# main.net
KiCad netlist of a schematic drawn in Altium Designer
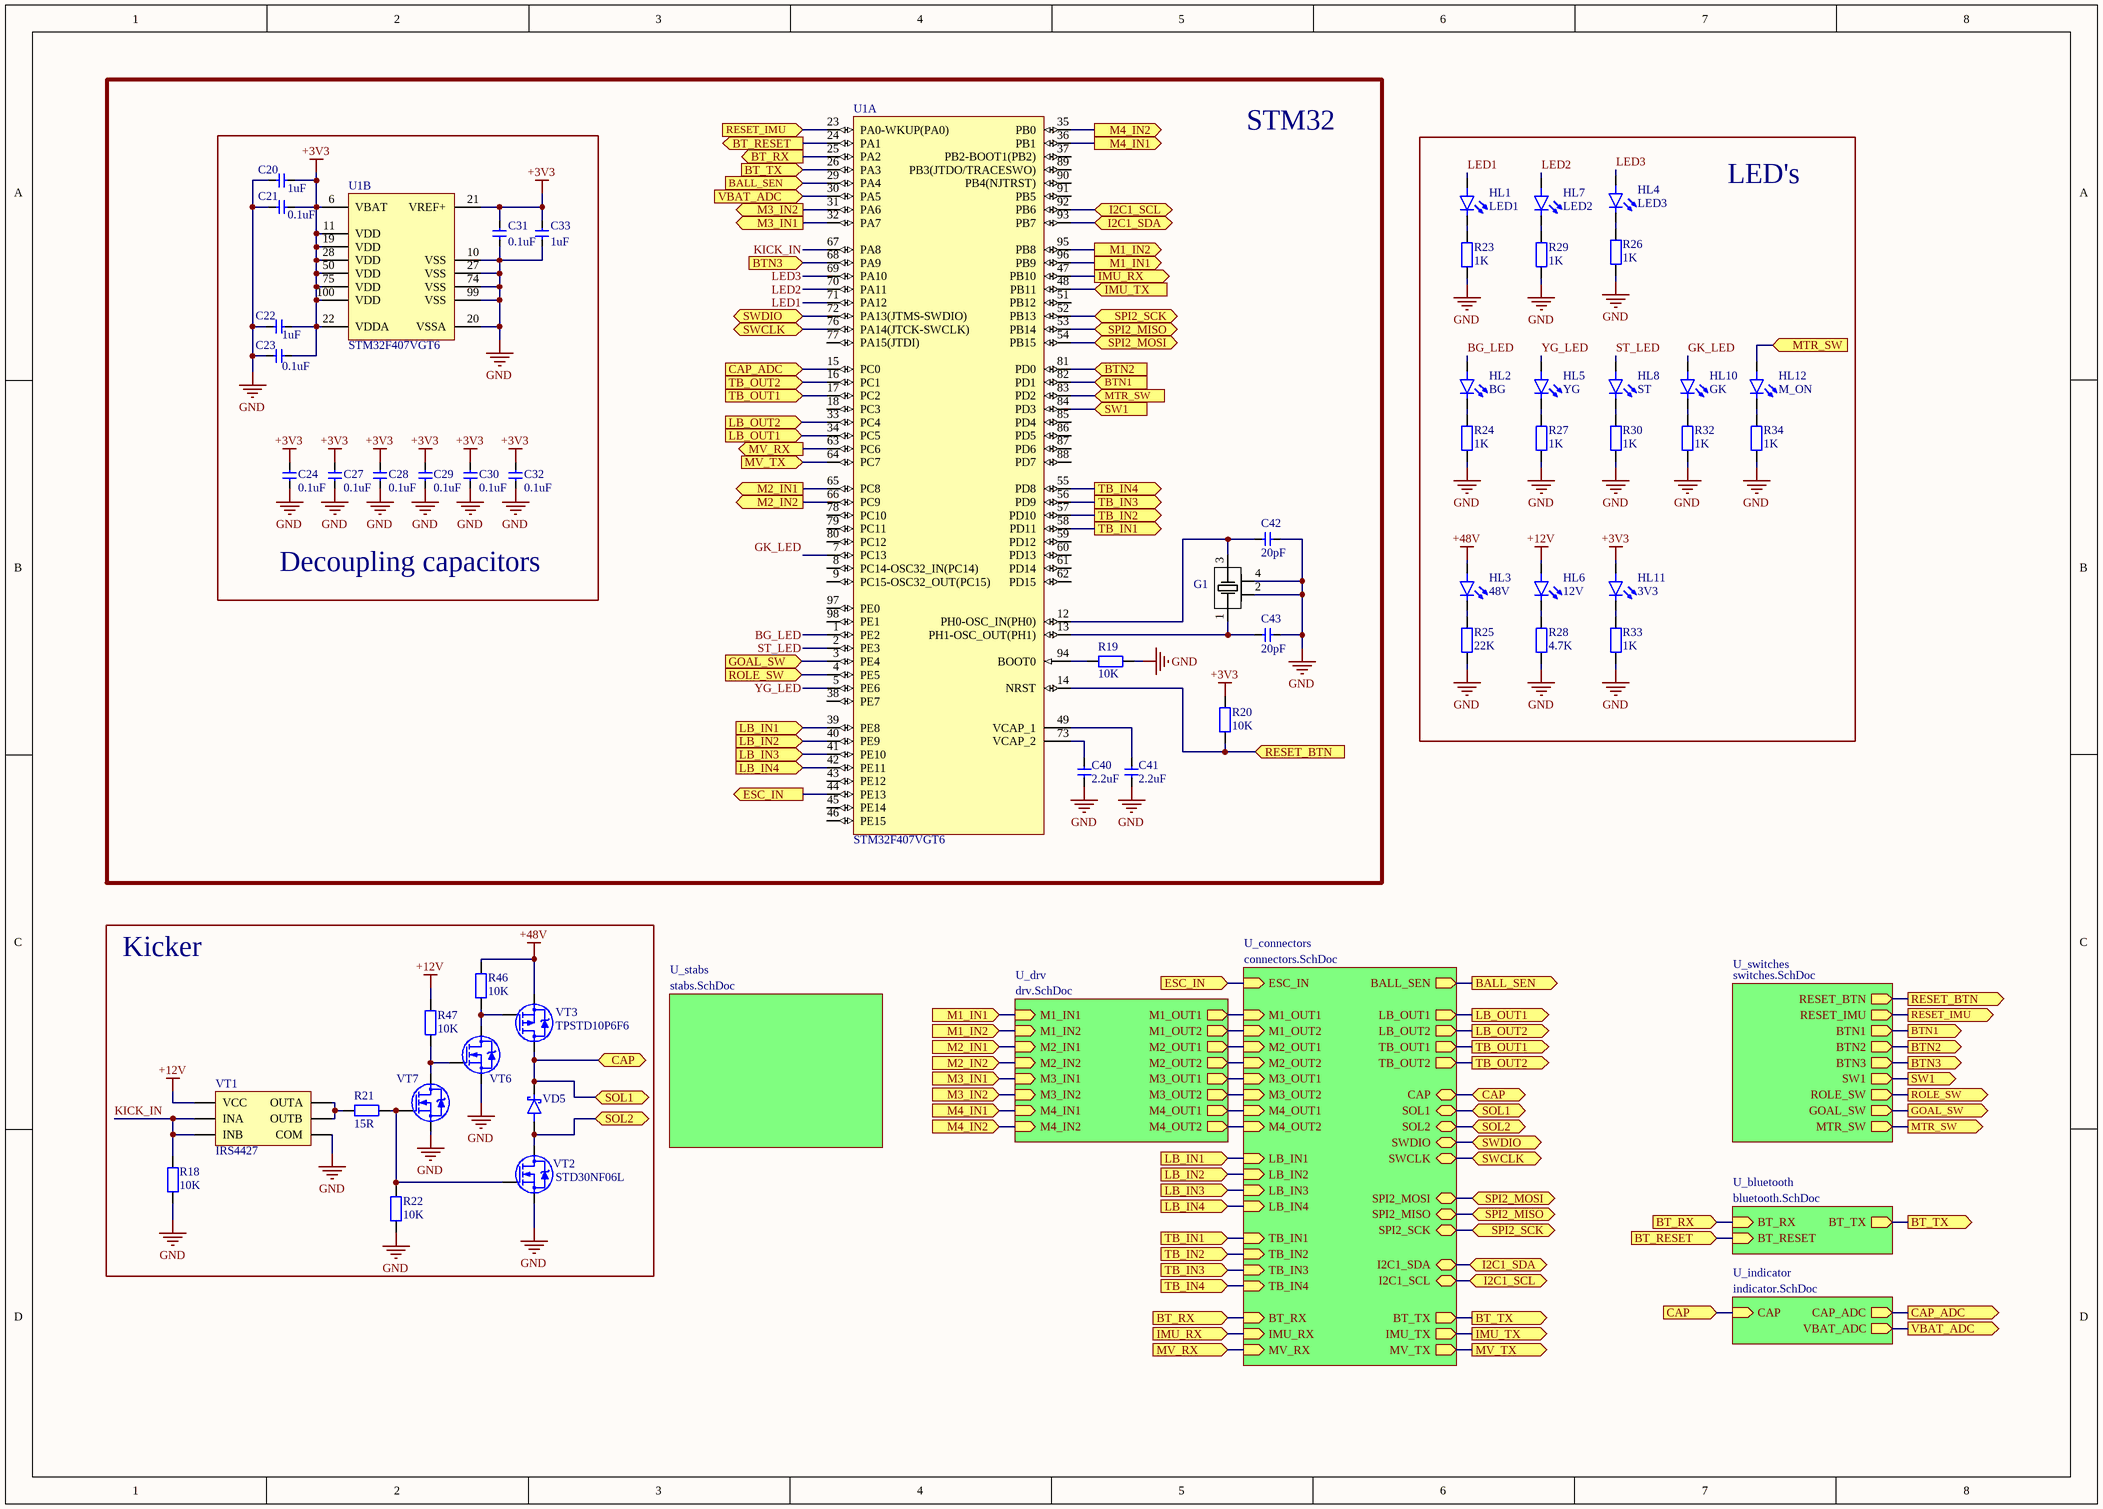
[diagram p0: main.SchDoc]

(export (version "E")
  (design (tool "Eeschema 10.0.6"))
  (components
    (comp (ref "C20")
      (value "1uF")
      (footprint "CAP0805")
      (description "Ceramic SMD Cap")
      (libsource (lib "") (part "CAP Ceramic_1"))
    )
    (comp (ref "C21")
      (value "0.1uF")
      (footprint "CAP0805")
      (description "Ceramic SMD Cap")
      (libsource (lib "") (part "CAP Ceramic_1"))
    )
    (comp (ref "C22")
      (value "1uF")
      (footprint "CAP0805")
      (description "Ceramic SMD Cap")
      (libsource (lib "") (part "CAP Ceramic_1"))
    )
    (comp (ref "C23")
      (value "0.1uF")
      (footprint "CAP0805")
      (description "Ceramic SMD Cap")
      (libsource (lib "") (part "CAP Ceramic_1"))
    )
    (comp (ref "C24")
      (value "0.1uF")
      (footprint "CAP0805")
      (description "Ceramic SMD Cap")
      (libsource (lib "") (part "CAP Ceramic_1"))
    )
    (comp (ref "C27")
      (value "0.1uF")
      (footprint "CAP0805")
      (description "Ceramic SMD Cap")
      (libsource (lib "") (part "CAP Ceramic_1"))
    )
    (comp (ref "C28")
      (value "0.1uF")
      (footprint "CAP0805")
      (description "Ceramic SMD Cap")
      (libsource (lib "") (part "CAP Ceramic_1"))
    )
    (comp (ref "C29")
      (value "0.1uF")
      (footprint "CAP0805")
      (description "Ceramic SMD Cap")
      (libsource (lib "") (part "CAP Ceramic_1"))
    )
    (comp (ref "C30")
      (value "0.1uF")
      (footprint "CAP0805")
      (description "Ceramic SMD Cap")
      (libsource (lib "") (part "CAP Ceramic_1"))
    )
    (comp (ref "C31")
      (value "0.1uF")
      (footprint "CAP0805")
      (description "Ceramic SMD Cap")
      (libsource (lib "") (part "CAP Ceramic_1"))
    )
    (comp (ref "C32")
      (value "0.1uF")
      (footprint "CAP0805")
      (description "Ceramic SMD Cap")
      (libsource (lib "") (part "CAP Ceramic_1"))
    )
    (comp (ref "C33")
      (value "1uF")
      (footprint "CAP0805")
      (description "Ceramic SMD Cap")
      (libsource (lib "") (part "CAP Ceramic_1"))
    )
    (comp (ref "C40")
      (value "2.2uF")
      (footprint "CAP0805")
      (description "Ceramic SMD Cap")
      (libsource (lib "Asterisk") (part "CAP Ceramic"))
    )
    (comp (ref "C41")
      (value "2.2uF")
      (footprint "CAP0805")
      (description "Ceramic SMD Cap")
      (libsource (lib "Asterisk") (part "CAP Ceramic"))
    )
    (comp (ref "C42")
      (value "20pF")
      (footprint "CAP0805")
      (description "Ceramic SMD Cap")
      (libsource (lib "") (part "CAP Ceramic_1"))
    )
    (comp (ref "C43")
      (value "20pF")
      (footprint "CAP0805")
      (description "Ceramic SMD Cap")
      (libsource (lib "") (part "CAP Ceramic_1"))
    )
    (comp (ref "G1")
      (value "8 MHz")
      (footprint "TSX-3225")
      (description "24MHz ±10ppm Crystal 9pF 40 Ohms 4-SMD, No Lead")
      (fields
        (field (name "PART NUMBER") "TSX-3225 24.0000MF15X-AC6")
        (field (name "DIGI-KEY PART NUMBER") "SER4180CT-ND")
      )
      (libsource (lib "SssAccesDatbase") (part "CTX957CT"))
    )
    (comp (ref "HL1")
      (value "LED1")
      (footprint "LED0603_WHITE")
      (description "LED smd")
      (libsource (lib "Asterisk") (part "LED"))
    )
    (comp (ref "HL2")
      (value "BG")
      (footprint "LED0603_WHITE")
      (description "LED smd")
      (libsource (lib "Asterisk") (part "LED"))
    )
    (comp (ref "HL3")
      (value "48V")
      (footprint "LED0603_GREEN")
      (description "LED smd")
      (libsource (lib "Asterisk") (part "LED"))
    )
    (comp (ref "HL4")
      (value "LED3")
      (footprint "LED0603_WHITE")
      (description "LED smd")
      (libsource (lib "Asterisk") (part "LED"))
    )
    (comp (ref "HL5")
      (value "YG")
      (footprint "LED0603_WHITE")
      (description "LED smd")
      (libsource (lib "Asterisk") (part "LED"))
    )
    (comp (ref "HL6")
      (value "12V")
      (footprint "LED0603_GREEN")
      (description "LED smd")
      (libsource (lib "Asterisk") (part "LED"))
    )
    (comp (ref "HL7")
      (value "LED2")
      (footprint "LED0603_WHITE")
      (description "LED smd")
      (libsource (lib "Asterisk") (part "LED"))
    )
    (comp (ref "HL8")
      (value "ST")
      (footprint "LED0603_WHITE")
      (description "LED smd")
      (libsource (lib "Asterisk") (part "LED"))
    )
    (comp (ref "HL10")
      (value "GK")
      (footprint "LED0603_WHITE")
      (description "LED smd")
      (libsource (lib "Asterisk") (part "LED"))
    )
    (comp (ref "HL11")
      (value "3V3")
      (footprint "LED0603_GREEN")
      (description "LED smd")
      (libsource (lib "Asterisk") (part "LED"))
    )
    (comp (ref "HL12")
      (value "M_ON")
      (footprint "LED0603_RED")
      (description "LED smd")
      (libsource (lib "Asterisk") (part "LED"))
    )
    (comp (ref "R18")
      (value "10K")
      (footprint "RES0805")
      (description "RES smd")
      (libsource (lib "Asterisk") (part "RES"))
    )
    (comp (ref "R19")
      (value "10K")
      (footprint "RES0805")
      (description "RES smd")
      (libsource (lib "Asterisk") (part "RES"))
    )
    (comp (ref "R20")
      (value "10K")
      (footprint "RES0805")
      (description "RES smd")
      (libsource (lib "Asterisk") (part "RES"))
    )
    (comp (ref "R21")
      (value "15R")
      (footprint "RES1206")
      (description "RES smd")
      (libsource (lib "Asterisk") (part "RES"))
    )
    (comp (ref "R22")
      (value "10K")
      (footprint "RES0805")
      (description "RES smd")
      (libsource (lib "Asterisk") (part "RES"))
    )
    (comp (ref "R23")
      (value "1K")
      (footprint "RES0805")
      (description "RES smd")
      (libsource (lib "Asterisk") (part "RES"))
    )
    (comp (ref "R24")
      (value "1K")
      (footprint "RES0805")
      (description "RES smd")
      (libsource (lib "Asterisk") (part "RES"))
    )
    (comp (ref "R25")
      (value "22K")
      (footprint "RES0805")
      (description "RES smd")
      (libsource (lib "Asterisk") (part "RES"))
    )
    (comp (ref "R26")
      (value "1K")
      (footprint "RES0805")
      (description "RES smd")
      (libsource (lib "Asterisk") (part "RES"))
    )
    (comp (ref "R27")
      (value "1K")
      (footprint "RES0805")
      (description "RES smd")
      (libsource (lib "Asterisk") (part "RES"))
    )
    (comp (ref "R28")
      (value "4.7K")
      (footprint "RES0805")
      (description "RES smd")
      (libsource (lib "Asterisk") (part "RES"))
    )
    (comp (ref "R29")
      (value "1K")
      (footprint "RES0805")
      (description "RES smd")
      (libsource (lib "Asterisk") (part "RES"))
    )
    (comp (ref "R30")
      (value "1K")
      (footprint "RES0805")
      (description "RES smd")
      (libsource (lib "Asterisk") (part "RES"))
    )
    (comp (ref "R32")
      (value "1K")
      (footprint "RES0805")
      (description "RES smd")
      (libsource (lib "Asterisk") (part "RES"))
    )
    (comp (ref "R33")
      (value "1K")
      (footprint "RES0805")
      (description "RES smd")
      (libsource (lib "Asterisk") (part "RES"))
    )
    (comp (ref "R34")
      (value "1K")
      (footprint "RES0805")
      (description "RES smd")
      (libsource (lib "Asterisk") (part "RES"))
    )
    (comp (ref "R46")
      (value "10K")
      (footprint "RES0805")
      (description "RES smd")
      (libsource (lib "Asterisk") (part "RES"))
    )
    (comp (ref "R47")
      (value "10K")
      (footprint "RES0805")
      (description "RES smd")
      (libsource (lib "Asterisk") (part "RES"))
    )
    (comp (ref "U1")
      (value "STM32F407VGT6")
      (footprint "LQFP100")
      (fields (field (name "MANUFACTURER") "STMicroelectronics"))
      (libsource (lib "Asterisk") (part "STM32F407VGT6"))
    )
    (comp (ref "VD5")
      (value "Diode Schottky")
      (footprint "DO-214AC (SMA)")
      (libsource (lib "Asterisk") (part "Diode Schottky"))
    )
    (comp (ref "VT1")
      (value "IRS4427")
      (footprint "SOIC-8")
      (description "Mosfet driver")
      (libsource (lib "Asterisk") (part "IRS4427"))
    )
    (comp (ref "VT2")
      (value "STD30NF06L")
      (footprint "DPAK")
      (description "N-MOSFET\r\nUds = 60 V\r\nIds = 30 A\r\nRds = 0.023 Ohm\r\nP = 55 W")
      (libsource (lib "Asterisk") (part "STD30NF06L"))
    )
    (comp (ref "VT3")
      (value "TPSTD10P6F6")
      (footprint "DPAK")
      (description "P-MOSFET\r\nUds = 60 V\r\nIds = 13 A\r\nRds = 0.100 Ohm\r\nP = 60 W")
      (libsource (lib "Asterisk") (part "TPSTD10P6F6"))
    )
    (comp (ref "VT6")
      (value "IRLML2502")
      (footprint "SOT-23-3")
      (description "N-MOSFET\r\nUds = 20 V\r\nIds = 4.2 A\r\nRds = 0.035 Ohm\r\nP = 1,25 W")
      (libsource (lib "Asterisk") (part "IRLML2502"))
    )
    (comp (ref "VT7")
      (value "IRLML2502")
      (footprint "SOT-23-3")
      (description "N-MOSFET\r\nUds = 20 V\r\nIds = 4.2 A\r\nRds = 0.035 Ohm\r\nP = 8 W")
      (libsource (lib "Asterisk") (part "IRLML2502"))
    )
  )
  (nets
    (net (code "1") (name "+3V3") (class "Default")
      (node (ref "C20") (pin "1") (pinfunction "1_1") (pintype "passive"))
      (node (ref "C21") (pin "1") (pinfunction "1_1") (pintype "passive"))
      (node (ref "C22") (pin "1") (pinfunction "1_1") (pintype "passive"))
      (node (ref "C23") (pin "1") (pinfunction "1_1") (pintype "passive"))
      (node (ref "C24") (pin "1") (pinfunction "1_1") (pintype "passive"))
      (node (ref "C27") (pin "1") (pinfunction "1_1") (pintype "passive"))
      (node (ref "C28") (pin "1") (pinfunction "1_1") (pintype "passive"))
      (node (ref "C29") (pin "1") (pinfunction "1_1") (pintype "passive"))
      (node (ref "C30") (pin "1") (pinfunction "1_1") (pintype "passive"))
      (node (ref "C31") (pin "2") (pinfunction "2_2") (pintype "passive"))
      (node (ref "C32") (pin "1") (pinfunction "1_1") (pintype "passive"))
      (node (ref "C33") (pin "2") (pinfunction "2_2") (pintype "passive"))
      (node (ref "HL11") (pin "2") (pinfunction "A_2") (pintype "passive"))
      (node (ref "R20") (pin "1") (pinfunction "1_1") (pintype "passive"))
      (node (ref "U1") (pin "100") (pinfunction "VDD_100") (pintype "power_in"))
      (node (ref "U1") (pin "11") (pinfunction "VDD_11") (pintype "power_in"))
      (node (ref "U1") (pin "19") (pinfunction "VDD_19") (pintype "power_in"))
      (node (ref "U1") (pin "21") (pinfunction "VREF+_21") (pintype "power_in"))
      (node (ref "U1") (pin "22") (pinfunction "VDDA_22") (pintype "power_in"))
      (node (ref "U1") (pin "28") (pinfunction "VDD_28") (pintype "power_in"))
      (node (ref "U1") (pin "50") (pinfunction "VDD_50") (pintype "power_in"))
      (node (ref "U1") (pin "6") (pinfunction "VBAT_6") (pintype "power_in"))
      (node (ref "U1") (pin "75") (pinfunction "VDD_75") (pintype "power_in"))
    )
    (net (code "2") (name "+12V") (class "Default")
      (node (ref "HL6") (pin "2") (pinfunction "A_2") (pintype "passive"))
      (node (ref "R47") (pin "2") (pinfunction "2_2") (pintype "passive"))
      (node (ref "VT1") (pin "6") (pinfunction "VCC_6") (pintype "passive"))
    )
    (net (code "3") (name "+48V") (class "Default")
      (node (ref "HL3") (pin "2") (pinfunction "A_2") (pintype "passive"))
      (node (ref "R46") (pin "2") (pinfunction "2_2") (pintype "passive"))
      (node (ref "VT3") (pin "S") (pinfunction "S_S") (pintype "passive"))
    )
    (net (code "4") (name "/BALL_SEN") (class "Default")
      (node (ref "U1") (pin "29") (pinfunction "PA4_29") (pintype "bidirectional"))
    )
    (net (code "5") (name "/BG_LED") (class "Default")
      (node (ref "HL2") (pin "2") (pinfunction "A_2") (pintype "passive"))
      (node (ref "U1") (pin "1") (pinfunction "PE2_1") (pintype "bidirectional"))
    )
    (net (code "6") (name "/BTN1") (class "Default")
      (node (ref "U1") (pin "82") (pinfunction "PD1_82") (pintype "bidirectional"))
    )
    (net (code "7") (name "/BTN2") (class "Default")
      (node (ref "U1") (pin "81") (pinfunction "PD0_81") (pintype "bidirectional"))
    )
    (net (code "8") (name "/BTN3") (class "Default")
      (node (ref "U1") (pin "68") (pinfunction "PA9_68") (pintype "bidirectional"))
    )
    (net (code "9") (name "/BT_RESET") (class "Default")
      (node (ref "U1") (pin "24") (pinfunction "PA1_24") (pintype "bidirectional"))
    )
    (net (code "10") (name "/BT_RX") (class "Default")
      (node (ref "U1") (pin "25") (pinfunction "PA2_25") (pintype "bidirectional"))
    )
    (net (code "11") (name "/BT_TX") (class "Default")
      (node (ref "U1") (pin "26") (pinfunction "PA3_26") (pintype "bidirectional"))
    )
    (net (code "12") (name "/CAP") (class "Default")
      (node (ref "VD5") (pin "K") (pinfunction "K_K") (pintype "passive"))
      (node (ref "VT3") (pin "D") (pinfunction "D_D") (pintype "passive"))
    )
    (net (code "13") (name "/CAP_ADC") (class "Default")
      (node (ref "U1") (pin "15") (pinfunction "PC0_15") (pintype "bidirectional"))
    )
    (net (code "14") (name "/ESC_IN") (class "Default")
      (node (ref "U1") (pin "44") (pinfunction "PE13_44") (pintype "bidirectional"))
    )
    (net (code "15") (name "/GK_LED") (class "Default")
      (node (ref "HL10") (pin "2") (pinfunction "A_2") (pintype "passive"))
      (node (ref "U1") (pin "7") (pinfunction "PC13_7") (pintype "bidirectional"))
    )
    (net (code "16") (name "/GOAL_SW") (class "Default")
      (node (ref "U1") (pin "3") (pinfunction "PE4_3") (pintype "bidirectional"))
    )
    (net (code "17") (name "/I2C1_SCL") (class "Default")
      (node (ref "U1") (pin "92") (pinfunction "PB6_92") (pintype "bidirectional"))
    )
    (net (code "18") (name "/I2C1_SDA") (class "Default")
      (node (ref "U1") (pin "93") (pinfunction "PB7_93") (pintype "bidirectional"))
    )
    (net (code "19") (name "/IMU_RX") (class "Default")
      (node (ref "U1") (pin "47") (pinfunction "PB10_47") (pintype "bidirectional"))
    )
    (net (code "20") (name "/IMU_TX") (class "Default")
      (node (ref "U1") (pin "48") (pinfunction "PB11_48") (pintype "bidirectional"))
    )
    (net (code "21") (name "/KICK_IN") (class "Default")
      (node (ref "R18") (pin "2") (pinfunction "2_2") (pintype "passive"))
      (node (ref "U1") (pin "67") (pinfunction "PA8_67") (pintype "bidirectional"))
      (node (ref "VT1") (pin "2") (pinfunction "INA_2") (pintype "passive"))
      (node (ref "VT1") (pin "4") (pinfunction "INB_4") (pintype "passive"))
    )
    (net (code "22") (name "/LB_IN1") (class "Default")
      (node (ref "U1") (pin "39") (pinfunction "PE8_39") (pintype "bidirectional"))
    )
    (net (code "23") (name "/LB_IN2") (class "Default")
      (node (ref "U1") (pin "40") (pinfunction "PE9_40") (pintype "bidirectional"))
    )
    (net (code "24") (name "/LB_IN3") (class "Default")
      (node (ref "U1") (pin "41") (pinfunction "PE10_41") (pintype "bidirectional"))
    )
    (net (code "25") (name "/LB_IN4") (class "Default")
      (node (ref "U1") (pin "42") (pinfunction "PE11_42") (pintype "bidirectional"))
    )
    (net (code "26") (name "/LB_OUT1") (class "Default")
      (node (ref "U1") (pin "34") (pinfunction "PC5_34") (pintype "bidirectional"))
    )
    (net (code "27") (name "/LB_OUT2") (class "Default")
      (node (ref "U1") (pin "33") (pinfunction "PC4_33") (pintype "bidirectional"))
    )
    (net (code "28") (name "/LED1") (class "Default")
      (node (ref "HL1") (pin "2") (pinfunction "A_2") (pintype "passive"))
      (node (ref "U1") (pin "71") (pinfunction "PA12_71") (pintype "bidirectional"))
    )
    (net (code "29") (name "/LED2") (class "Default")
      (node (ref "HL7") (pin "2") (pinfunction "A_2") (pintype "passive"))
      (node (ref "U1") (pin "70") (pinfunction "PA11_70") (pintype "bidirectional"))
    )
    (net (code "30") (name "/LED3") (class "Default")
      (node (ref "HL4") (pin "2") (pinfunction "A_2") (pintype "passive"))
      (node (ref "U1") (pin "69") (pinfunction "PA10_69") (pintype "bidirectional"))
    )
    (net (code "31") (name "/M1_IN1") (class "Default")
      (node (ref "U1") (pin "96") (pinfunction "PB9_96") (pintype "bidirectional"))
    )
    (net (code "32") (name "/M1_IN2") (class "Default")
      (node (ref "U1") (pin "95") (pinfunction "PB8_95") (pintype "bidirectional"))
    )
    (net (code "35") (name "/M2_IN1") (class "Default")
      (node (ref "U1") (pin "65") (pinfunction "PC8_65") (pintype "bidirectional"))
    )
    (net (code "36") (name "/M2_IN2") (class "Default")
      (node (ref "U1") (pin "66") (pinfunction "PC9_66") (pintype "bidirectional"))
    )
    (net (code "39") (name "/M3_IN1") (class "Default")
      (node (ref "U1") (pin "32") (pinfunction "PA7_32") (pintype "bidirectional"))
    )
    (net (code "40") (name "/M3_IN2") (class "Default")
      (node (ref "U1") (pin "31") (pinfunction "PA6_31") (pintype "bidirectional"))
    )
    (net (code "43") (name "/M4_IN1") (class "Default")
      (node (ref "U1") (pin "36") (pinfunction "PB1_36") (pintype "bidirectional"))
    )
    (net (code "44") (name "/M4_IN2") (class "Default")
      (node (ref "U1") (pin "35") (pinfunction "PB0_35") (pintype "bidirectional"))
    )
    (net (code "47") (name "/MTR_SW") (class "Default")
      (node (ref "HL12") (pin "2") (pinfunction "A_2") (pintype "passive"))
      (node (ref "U1") (pin "83") (pinfunction "PD2_83") (pintype "bidirectional"))
    )
    (net (code "48") (name "/MV_RX") (class "Default")
      (node (ref "U1") (pin "63") (pinfunction "PC6_63") (pintype "bidirectional"))
    )
    (net (code "49") (name "/MV_TX") (class "Default")
      (node (ref "U1") (pin "64") (pinfunction "PC7_64") (pintype "bidirectional"))
    )
    (net (code "50") (name "/RESET_BTN") (class "Default")
      (node (ref "R20") (pin "2") (pinfunction "2_2") (pintype "passive"))
      (node (ref "U1") (pin "14") (pinfunction "NRST_14") (pintype "bidirectional"))
    )
    (net (code "51") (name "/RESET_IMU") (class "Default")
      (node (ref "U1") (pin "23") (pinfunction "PA0-WKUP(PA0)_23") (pintype "bidirectional"))
    )
    (net (code "52") (name "/ROLE_SW") (class "Default")
      (node (ref "U1") (pin "4") (pinfunction "PE5_4") (pintype "bidirectional"))
    )
    (net (code "53") (name "/SOL2") (class "Default")
      (node (ref "VD5") (pin "A") (pinfunction "A_A") (pintype "passive"))
      (node (ref "VT2") (pin "D") (pinfunction "D_D") (pintype "passive"))
    )
    (net (code "54") (name "/SPI2_MISO") (class "Default")
      (node (ref "U1") (pin "53") (pinfunction "PB14_53") (pintype "bidirectional"))
    )
    (net (code "55") (name "/SPI2_MOSI") (class "Default")
      (node (ref "U1") (pin "54") (pinfunction "PB15_54") (pintype "bidirectional"))
    )
    (net (code "56") (name "/SPI2_SCK") (class "Default")
      (node (ref "U1") (pin "52") (pinfunction "PB13_52") (pintype "bidirectional"))
    )
    (net (code "57") (name "/ST_LED") (class "Default")
      (node (ref "HL8") (pin "2") (pinfunction "A_2") (pintype "passive"))
      (node (ref "U1") (pin "2") (pinfunction "PE3_2") (pintype "bidirectional"))
    )
    (net (code "58") (name "/SW1") (class "Default")
      (node (ref "U1") (pin "84") (pinfunction "PD3_84") (pintype "bidirectional"))
    )
    (net (code "59") (name "/SWCLK") (class "Default")
      (node (ref "U1") (pin "76") (pinfunction "PA14(JTCK-SWCLK)_76") (pintype "bidirectional"))
    )
    (net (code "60") (name "/SWDIO") (class "Default")
      (node (ref "U1") (pin "72") (pinfunction "PA13(JTMS-SWDIO)_72") (pintype "bidirectional"))
    )
    (net (code "61") (name "/TB_IN1") (class "Default")
      (node (ref "U1") (pin "58") (pinfunction "PD11_58") (pintype "bidirectional"))
    )
    (net (code "62") (name "/TB_IN2") (class "Default")
      (node (ref "U1") (pin "57") (pinfunction "PD10_57") (pintype "bidirectional"))
    )
    (net (code "63") (name "/TB_IN3") (class "Default")
      (node (ref "U1") (pin "56") (pinfunction "PD9_56") (pintype "bidirectional"))
    )
    (net (code "64") (name "/TB_IN4") (class "Default")
      (node (ref "U1") (pin "55") (pinfunction "PD8_55") (pintype "bidirectional"))
    )
    (net (code "65") (name "/TB_OUT1") (class "Default")
      (node (ref "U1") (pin "17") (pinfunction "PC2_17") (pintype "bidirectional"))
    )
    (net (code "66") (name "/TB_OUT2") (class "Default")
      (node (ref "U1") (pin "16") (pinfunction "PC1_16") (pintype "bidirectional"))
    )
    (net (code "67") (name "/VBAT_ADC") (class "Default")
      (node (ref "U1") (pin "30") (pinfunction "PA5_30") (pintype "bidirectional"))
    )
    (net (code "68") (name "/YG_LED") (class "Default")
      (node (ref "HL5") (pin "2") (pinfunction "A_2") (pintype "passive"))
      (node (ref "U1") (pin "5") (pinfunction "PE6_5") (pintype "bidirectional"))
    )
    (net (code "69") (name "GND") (class "Default")
      (node (ref "C20") (pin "2") (pinfunction "2_2") (pintype "passive"))
      (node (ref "C21") (pin "2") (pinfunction "2_2") (pintype "passive"))
      (node (ref "C22") (pin "2") (pinfunction "2_2") (pintype "passive"))
      (node (ref "C23") (pin "2") (pinfunction "2_2") (pintype "passive"))
      (node (ref "C24") (pin "2") (pinfunction "2_2") (pintype "passive"))
      (node (ref "C27") (pin "2") (pinfunction "2_2") (pintype "passive"))
      (node (ref "C28") (pin "2") (pinfunction "2_2") (pintype "passive"))
      (node (ref "C29") (pin "2") (pinfunction "2_2") (pintype "passive"))
      (node (ref "C30") (pin "2") (pinfunction "2_2") (pintype "passive"))
      (node (ref "C31") (pin "1") (pinfunction "1_1") (pintype "passive"))
      (node (ref "C32") (pin "2") (pinfunction "2_2") (pintype "passive"))
      (node (ref "C33") (pin "1") (pinfunction "1_1") (pintype "passive"))
      (node (ref "C40") (pin "1") (pinfunction "1_1") (pintype "passive"))
      (node (ref "C41") (pin "1") (pinfunction "1_1") (pintype "passive"))
      (node (ref "C42") (pin "2") (pinfunction "2_2") (pintype "passive"))
      (node (ref "C43") (pin "2") (pinfunction "2_2") (pintype "passive"))
      (node (ref "G1") (pin "2") (pinfunction "2_2") (pintype "passive"))
      (node (ref "G1") (pin "4") (pinfunction "4_4") (pintype "passive"))
      (node (ref "R18") (pin "1") (pinfunction "1_1") (pintype "passive"))
      (node (ref "R19") (pin "1") (pinfunction "1_1") (pintype "passive"))
      (node (ref "R22") (pin "1") (pinfunction "1_1") (pintype "passive"))
      (node (ref "R23") (pin "1") (pinfunction "1_1") (pintype "passive"))
      (node (ref "R24") (pin "1") (pinfunction "1_1") (pintype "passive"))
      (node (ref "R25") (pin "1") (pinfunction "1_1") (pintype "passive"))
      (node (ref "R26") (pin "1") (pinfunction "1_1") (pintype "passive"))
      (node (ref "R27") (pin "1") (pinfunction "1_1") (pintype "passive"))
      (node (ref "R28") (pin "1") (pinfunction "1_1") (pintype "passive"))
      (node (ref "R29") (pin "1") (pinfunction "1_1") (pintype "passive"))
      (node (ref "R30") (pin "1") (pinfunction "1_1") (pintype "passive"))
      (node (ref "R32") (pin "1") (pinfunction "1_1") (pintype "passive"))
      (node (ref "R33") (pin "1") (pinfunction "1_1") (pintype "passive"))
      (node (ref "R34") (pin "1") (pinfunction "1_1") (pintype "passive"))
      (node (ref "U1") (pin "10") (pinfunction "VSS_10") (pintype "power_in"))
      (node (ref "U1") (pin "20") (pinfunction "VSSA_20") (pintype "power_in"))
      (node (ref "U1") (pin "27") (pinfunction "VSS_27") (pintype "power_in"))
      (node (ref "U1") (pin "74") (pinfunction "VSS_74") (pintype "power_in"))
      (node (ref "U1") (pin "99") (pinfunction "VSS_99") (pintype "power_in"))
      (node (ref "VT1") (pin "3") (pinfunction "COM_3") (pintype "passive"))
      (node (ref "VT2") (pin "S") (pinfunction "S_S") (pintype "passive"))
      (node (ref "VT6") (pin "S") (pinfunction "S_S") (pintype "passive"))
      (node (ref "VT7") (pin "S") (pinfunction "S_S") (pintype "passive"))
    )
    (net (code "70") (name "Net-(HL1-K)") (class "Default")
      (node (ref "HL1") (pin "1") (pinfunction "K_1") (pintype "passive"))
      (node (ref "R23") (pin "2") (pinfunction "2_2") (pintype "passive"))
    )
    (net (code "71") (name "Net-(HL2-K)") (class "Default")
      (node (ref "HL2") (pin "1") (pinfunction "K_1") (pintype "passive"))
      (node (ref "R24") (pin "2") (pinfunction "2_2") (pintype "passive"))
    )
    (net (code "72") (name "Net-(HL3-K)") (class "Default")
      (node (ref "HL3") (pin "1") (pinfunction "K_1") (pintype "passive"))
      (node (ref "R25") (pin "2") (pinfunction "2_2") (pintype "passive"))
    )
    (net (code "73") (name "Net-(HL4-K)") (class "Default")
      (node (ref "HL4") (pin "1") (pinfunction "K_1") (pintype "passive"))
      (node (ref "R26") (pin "2") (pinfunction "2_2") (pintype "passive"))
    )
    (net (code "74") (name "Net-(HL5-K)") (class "Default")
      (node (ref "HL5") (pin "1") (pinfunction "K_1") (pintype "passive"))
      (node (ref "R27") (pin "2") (pinfunction "2_2") (pintype "passive"))
    )
    (net (code "75") (name "Net-(HL6-K)") (class "Default")
      (node (ref "HL6") (pin "1") (pinfunction "K_1") (pintype "passive"))
      (node (ref "R28") (pin "2") (pinfunction "2_2") (pintype "passive"))
    )
    (net (code "76") (name "Net-(HL7-K)") (class "Default")
      (node (ref "HL7") (pin "1") (pinfunction "K_1") (pintype "passive"))
      (node (ref "R29") (pin "2") (pinfunction "2_2") (pintype "passive"))
    )
    (net (code "77") (name "Net-(HL8-K)") (class "Default")
      (node (ref "HL8") (pin "1") (pinfunction "K_1") (pintype "passive"))
      (node (ref "R30") (pin "2") (pinfunction "2_2") (pintype "passive"))
    )
    (net (code "78") (name "Net-(HL10-K)") (class "Default")
      (node (ref "HL10") (pin "1") (pinfunction "K_1") (pintype "passive"))
      (node (ref "R32") (pin "2") (pinfunction "2_2") (pintype "passive"))
    )
    (net (code "79") (name "Net-(HL11-K)") (class "Default")
      (node (ref "HL11") (pin "1") (pinfunction "K_1") (pintype "passive"))
      (node (ref "R33") (pin "2") (pinfunction "2_2") (pintype "passive"))
    )
    (net (code "80") (name "Net-(HL12-K)") (class "Default")
      (node (ref "HL12") (pin "1") (pinfunction "K_1") (pintype "passive"))
      (node (ref "R34") (pin "2") (pinfunction "2_2") (pintype "passive"))
    )
    (net (code "81") (name "Net-(R21-Pad2)") (class "Default")
      (node (ref "R21") (pin "2") (pinfunction "2_2") (pintype "passive"))
      (node (ref "R22") (pin "2") (pinfunction "2_2") (pintype "passive"))
      (node (ref "VT2") (pin "G") (pinfunction "G_G") (pintype "passive"))
      (node (ref "VT7") (pin "G") (pinfunction "G_G") (pintype "passive"))
    )
    (net (code "82") (name "Net-(R46-Pad1)") (class "Default")
      (node (ref "R46") (pin "1") (pinfunction "1_1") (pintype "passive"))
      (node (ref "VT3") (pin "G") (pinfunction "G_G") (pintype "passive"))
      (node (ref "VT6") (pin "D") (pinfunction "D_D") (pintype "passive"))
    )
    (net (code "83") (name "Net-(R47-Pad1)") (class "Default")
      (node (ref "R47") (pin "1") (pinfunction "1_1") (pintype "passive"))
      (node (ref "VT6") (pin "G") (pinfunction "G_G") (pintype "passive"))
      (node (ref "VT7") (pin "D") (pinfunction "D_D") (pintype "passive"))
    )
    (net (code "84") (name "Net-(U1A-BOOT0)") (class "Default")
      (node (ref "R19") (pin "2") (pinfunction "2_2") (pintype "passive"))
      (node (ref "U1") (pin "94") (pinfunction "BOOT0_94") (pintype "input"))
    )
    (net (code "85") (name "Net-(U1A-PH0-OSC_IN(PH0))") (class "Default")
      (node (ref "C42") (pin "1") (pinfunction "1_1") (pintype "passive"))
      (node (ref "G1") (pin "3") (pinfunction "3_3") (pintype "passive"))
      (node (ref "U1") (pin "12") (pinfunction "PH0-OSC_IN(PH0)_12") (pintype "bidirectional"))
    )
    (net (code "86") (name "Net-(U1A-PH1-OSC_OUT(PH1))") (class "Default")
      (node (ref "C43") (pin "1") (pinfunction "1_1") (pintype "passive"))
      (node (ref "G1") (pin "1") (pinfunction "1_1") (pintype "passive"))
      (node (ref "U1") (pin "13") (pinfunction "PH1-OSC_OUT(PH1)_13") (pintype "bidirectional"))
    )
    (net (code "87") (name "Net-(U1A-VCAP_1)") (class "Default")
      (node (ref "C41") (pin "2") (pinfunction "2_2") (pintype "passive"))
      (node (ref "U1") (pin "49") (pinfunction "VCAP_1_49") (pintype "power_in"))
    )
    (net (code "88") (name "Net-(U1A-VCAP_2)") (class "Default")
      (node (ref "C40") (pin "2") (pinfunction "2_2") (pintype "passive"))
      (node (ref "U1") (pin "73") (pinfunction "VCAP_2_73") (pintype "power_in"))
    )
    (net (code "89") (name "Net-(VT1-OUTA)") (class "Default")
      (node (ref "R21") (pin "1") (pinfunction "1_1") (pintype "passive"))
      (node (ref "VT1") (pin "5") (pinfunction "OUTB_5") (pintype "passive"))
      (node (ref "VT1") (pin "7") (pinfunction "OUTA_7") (pintype "passive"))
    )
    (net (code "90") (name "unconnected-(U1A-PA15(JTDI)-Pad77)") (class "Default")
      (node (ref "U1") (pin "77") (pinfunction "PA15(JTDI)_77") (pintype "bidirectional"))
    )
    (net (code "91") (name "unconnected-(U1A-PB2-BOOT1(PB2)-Pad37)") (class "Default")
      (node (ref "U1") (pin "37") (pinfunction "PB2-BOOT1(PB2)_37") (pintype "bidirectional"))
    )
    (net (code "92") (name "unconnected-(U1A-PB3(JTDO{slash}TRACESWO)-Pad89)") (class "Default")
      (node (ref "U1") (pin "89") (pinfunction "PB3(JTDO/TRACESWO)_89") (pintype "bidirectional"))
    )
    (net (code "93") (name "unconnected-(U1A-PB4(NJTRST)-Pad90)") (class "Default")
      (node (ref "U1") (pin "90") (pinfunction "PB4(NJTRST)_90") (pintype "bidirectional"))
    )
    (net (code "94") (name "unconnected-(U1A-PB5-Pad91)") (class "Default")
      (node (ref "U1") (pin "91") (pinfunction "PB5_91") (pintype "bidirectional"))
    )
    (net (code "95") (name "unconnected-(U1A-PB12-Pad51)") (class "Default")
      (node (ref "U1") (pin "51") (pinfunction "PB12_51") (pintype "bidirectional"))
    )
    (net (code "96") (name "unconnected-(U1A-PC3-Pad18)") (class "Default")
      (node (ref "U1") (pin "18") (pinfunction "PC3_18") (pintype "bidirectional"))
    )
    (net (code "97") (name "unconnected-(U1A-PC10-Pad78)") (class "Default")
      (node (ref "U1") (pin "78") (pinfunction "PC10_78") (pintype "bidirectional"))
    )
    (net (code "98") (name "unconnected-(U1A-PC11-Pad79)") (class "Default")
      (node (ref "U1") (pin "79") (pinfunction "PC11_79") (pintype "bidirectional"))
    )
    (net (code "99") (name "unconnected-(U1A-PC12-Pad80)") (class "Default")
      (node (ref "U1") (pin "80") (pinfunction "PC12_80") (pintype "bidirectional"))
    )
    (net (code "100") (name "unconnected-(U1A-PC14-OSC32_IN(PC14)-Pad8)") (class "Default")
      (node (ref "U1") (pin "8") (pinfunction "PC14-OSC32_IN(PC14)_8") (pintype "bidirectional"))
    )
    (net (code "101") (name "unconnected-(U1A-PC15-OSC32_OUT(PC15)-Pad9)") (class "Default")
      (node (ref "U1") (pin "9") (pinfunction "PC15-OSC32_OUT(PC15)_9") (pintype "bidirectional"))
    )
    (net (code "102") (name "unconnected-(U1A-PD4-Pad85)") (class "Default")
      (node (ref "U1") (pin "85") (pinfunction "PD4_85") (pintype "bidirectional"))
    )
    (net (code "103") (name "unconnected-(U1A-PD5-Pad86)") (class "Default")
      (node (ref "U1") (pin "86") (pinfunction "PD5_86") (pintype "bidirectional"))
    )
    (net (code "104") (name "unconnected-(U1A-PD6-Pad87)") (class "Default")
      (node (ref "U1") (pin "87") (pinfunction "PD6_87") (pintype "bidirectional"))
    )
    (net (code "105") (name "unconnected-(U1A-PD7-Pad88)") (class "Default")
      (node (ref "U1") (pin "88") (pinfunction "PD7_88") (pintype "bidirectional"))
    )
    (net (code "106") (name "unconnected-(U1A-PD12-Pad59)") (class "Default")
      (node (ref "U1") (pin "59") (pinfunction "PD12_59") (pintype "bidirectional"))
    )
    (net (code "107") (name "unconnected-(U1A-PD13-Pad60)") (class "Default")
      (node (ref "U1") (pin "60") (pinfunction "PD13_60") (pintype "bidirectional"))
    )
    (net (code "108") (name "unconnected-(U1A-PD14-Pad61)") (class "Default")
      (node (ref "U1") (pin "61") (pinfunction "PD14_61") (pintype "bidirectional"))
    )
    (net (code "109") (name "unconnected-(U1A-PD15-Pad62)") (class "Default")
      (node (ref "U1") (pin "62") (pinfunction "PD15_62") (pintype "bidirectional"))
    )
    (net (code "110") (name "unconnected-(U1A-PE0-Pad97)") (class "Default")
      (node (ref "U1") (pin "97") (pinfunction "PE0_97") (pintype "bidirectional"))
    )
    (net (code "111") (name "unconnected-(U1A-PE1-Pad98)") (class "Default")
      (node (ref "U1") (pin "98") (pinfunction "PE1_98") (pintype "bidirectional"))
    )
    (net (code "112") (name "unconnected-(U1A-PE7-Pad38)") (class "Default")
      (node (ref "U1") (pin "38") (pinfunction "PE7_38") (pintype "bidirectional"))
    )
    (net (code "113") (name "unconnected-(U1A-PE12-Pad43)") (class "Default")
      (node (ref "U1") (pin "43") (pinfunction "PE12_43") (pintype "bidirectional"))
    )
    (net (code "114") (name "unconnected-(U1A-PE14-Pad45)") (class "Default")
      (node (ref "U1") (pin "45") (pinfunction "PE14_45") (pintype "bidirectional"))
    )
    (net (code "115") (name "unconnected-(U1A-PE15-Pad46)") (class "Default")
      (node (ref "U1") (pin "46") (pinfunction "PE15_46") (pintype "bidirectional"))
    )
  )
)
